# UV_Sheet1.net
KiCad netlist of a schematic drawn in Altium Designer
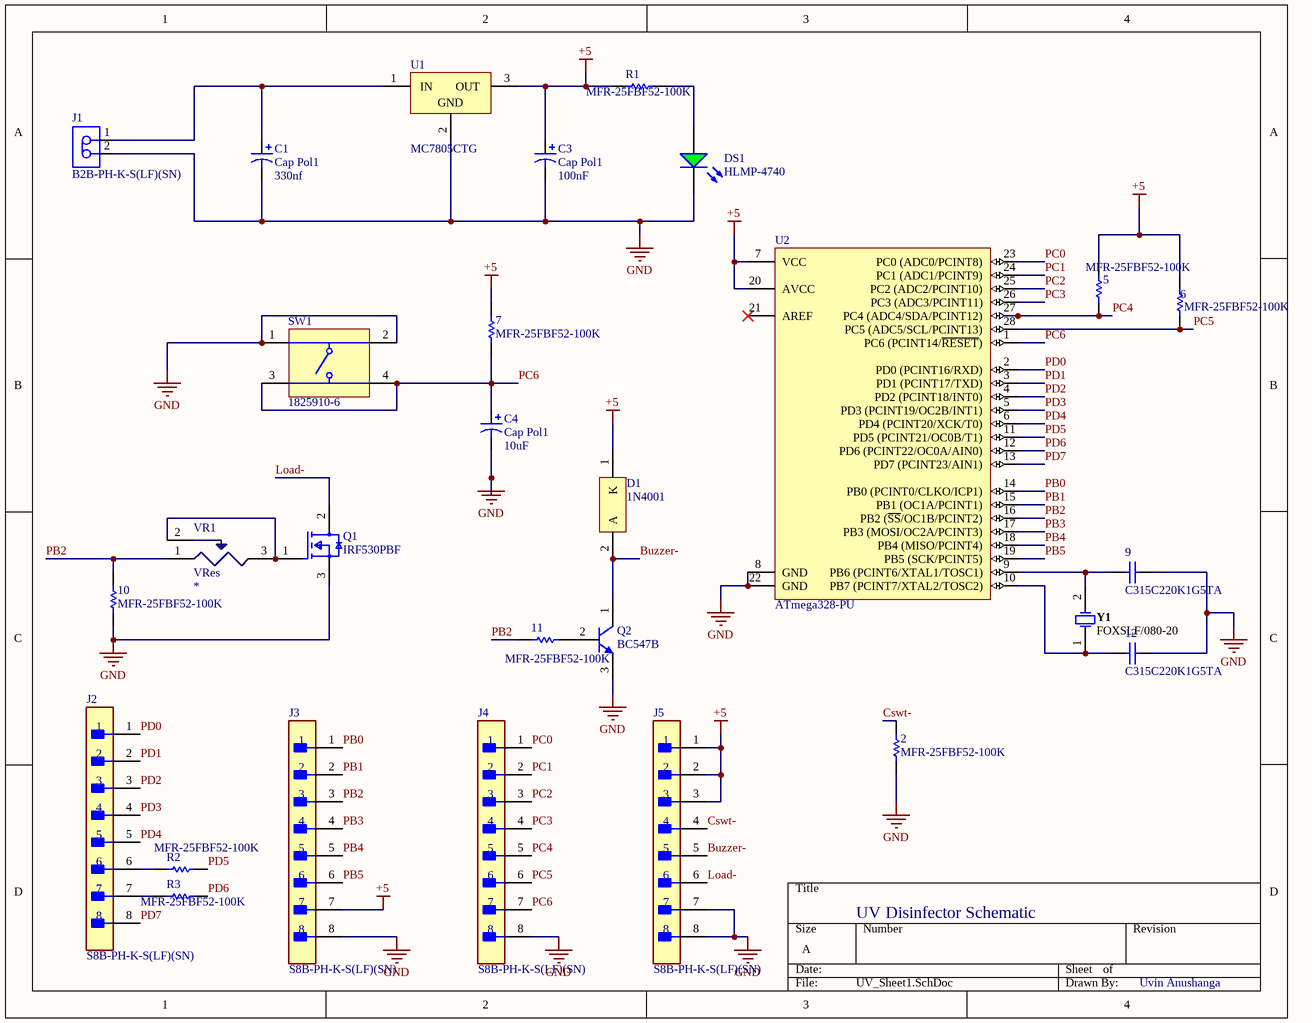
[diagram p0: UV_Sheet1.SchDoc]

(export (version "E")
  (design (tool "Eeschema 10.0.6"))
  (components
    (comp (ref "2")
      (value "MFR-25FBF52-100K")
      (footprint "RESA60-630X240")
      (description "Axial Resistor, 100 KOhm, +/- 1%, 0.25 W, -55 to 155 degC, 2-Pin THD, RoHS, Bulk")
      (fields (field (name "TOLERANCE") "1%"))
      (libsource (lib "Altium Content Vault") (part "RES-2"))
    )
    (comp (ref "5")
      (value "MFR-25FBF52-100K")
      (footprint "RESA60-630X240")
      (description "Axial Resistor, 100 KOhm, +/- 1%, 0.25 W, -55 to 155 degC, 2-Pin THD, RoHS, Bulk")
      (fields (field (name "TOLERANCE") "1%"))
      (libsource (lib "Altium Content Vault") (part "RES-2"))
    )
    (comp (ref "6")
      (value "MFR-25FBF52-100K")
      (footprint "RESA60-630X240")
      (description "Axial Resistor, 100 KOhm, +/- 1%, 0.25 W, -55 to 155 degC, 2-Pin THD, RoHS, Bulk")
      (fields (field (name "TOLERANCE") "1%"))
      (libsource (lib "Altium Content Vault") (part "RES-2"))
    )
    (comp (ref "7")
      (value "MFR-25FBF52-100K")
      (footprint "RESA60-630X240")
      (description "Axial Resistor, 100 KOhm, +/- 1%, 0.25 W, -55 to 155 degC, 2-Pin THD, RoHS, Bulk")
      (fields (field (name "TOLERANCE") "1%"))
      (libsource (lib "Altium Content Vault") (part "RES-2"))
    )
    (comp (ref "9")
      (value "C315C220K1G5TA")
      (footprint "KEMT-C315-THT-2")
      (description "Capacitor, Ceramic, 22 pF, +/-10 %, 100 V, -55 to 125 degC, 2-Pin THD, RoHS, Bulk")
      (libsource (lib "Altium Content Vault") (part "CAP-NP-2"))
    )
    (comp (ref "10")
      (value "MFR-25FBF52-100K")
      (footprint "RESA60-630X240")
      (description "Axial Resistor, 100 KOhm, +/- 1%, 0.25 W, -55 to 155 degC, 2-Pin THD, RoHS, Bulk")
      (fields (field (name "TOLERANCE") "1%"))
      (libsource (lib "Altium Content Vault") (part "RES-2"))
    )
    (comp (ref "11")
      (value "MFR-25FBF52-100K")
      (footprint "RESA60-630X240")
      (description "Axial Resistor, 100 KOhm, +/- 1%, 0.25 W, -55 to 155 degC, 2-Pin THD, RoHS, Bulk")
      (fields (field (name "TOLERANCE") "1%"))
      (libsource (lib "Altium Content Vault") (part "RES-2"))
    )
    (comp (ref "12")
      (value "C315C220K1G5TA")
      (footprint "KEMT-C315-THT-2")
      (description "Capacitor, Ceramic, 22 pF, +/-10 %, 100 V, -55 to 125 degC, 2-Pin THD, RoHS, Bulk")
      (libsource (lib "Altium Content Vault") (part "CAP-NP-2"))
    )
    (comp (ref "C1")
      (value "Cap Pol1")
      (footprint "RB7.6-15")
      (description "Polarized Capacitor (Radial)")
      (fields (field (name "ALTIUM_VALUE") "330nf") (field (name "PUBLISHER") "Altium Limited"))
      (libsource (lib "Miscellaneous Devices") (part "Cap Pol1"))
    )
    (comp (ref "C3")
      (value "Cap Pol1")
      (footprint "RB7.6-15")
      (description "Polarized Capacitor (Radial)")
      (fields (field (name "ALTIUM_VALUE") "100nF") (field (name "PUBLISHER") "Altium Limited"))
      (libsource (lib "Miscellaneous Devices") (part "Cap Pol1"))
    )
    (comp (ref "C4")
      (value "Cap Pol1")
      (footprint "RB7.6-15")
      (description "Polarized Capacitor (Radial)")
      (fields (field (name "ALTIUM_VALUE") "10uF") (field (name "PUBLISHER") "Altium Limited"))
      (libsource (lib "Miscellaneous Devices") (part "Cap Pol1"))
    )
    (comp (ref "D1")
      (value "1N4001")
      (footprint "ONSC-AXIAL_LEAD-2-59-10_P")
      (description "Standard Recovery Rectifier, 2-Pin Axial_Lead, Pb-Free, Bulk Bag")
      (fields (field (name "MANUFACTURER") "On Semiconductor"))
      (libsource (lib "Altium Content Vault") (part "ONSC-D-K1A2-2_A"))
    )
    (comp (ref "DS1")
      (value "HLMP-4740")
      (footprint "AVAG-HLMP-4740")
      (description "T-1 3/4 (5 mm) Low Current LED Lamp, Green, 1.9 V, -20 to 100 degC, 2-Pin THD, RoHS, Bulk")
      (fields (field (name "MANUFACTURER") "AvagoTechnologies"))
      (libsource (lib "Altium Content Vault") (part "LED-GREEN-AK-2"))
    )
    (comp (ref "J1")
      (value "B2B-PH-K-S(LF)(SN)")
      (footprint "JST-B2B-PH-K-S_V")
      (fields (field (name "MANUFACTURER") "JST"))
      (libsource (lib "Altium Content Vault") (part "CN-2P-F-QF2"))
    )
    (comp (ref "J2")
      (value "S8B-PH-K-S(LF)(SN)")
      (footprint "FP-S8B-PH-K-S_LF_SN-MFG")
      (description "CONN HEADER R/A 8POS 2MM")
      (libsource (lib "Altium Content Vault") (part "99ec2b232beb5d2356d4d77f6a047f0"))
    )
    (comp (ref "J3")
      (value "S8B-PH-K-S(LF)(SN)")
      (footprint "FP-S8B-PH-K-S_LF_SN-MFG")
      (description "CONN HEADER R/A 8POS 2MM")
      (libsource (lib "Altium Content Vault") (part "99ec2b232beb5d2356d4d77f6a047f0"))
    )
    (comp (ref "J4")
      (value "S8B-PH-K-S(LF)(SN)")
      (footprint "FP-S8B-PH-K-S_LF_SN-MFG")
      (description "CONN HEADER R/A 8POS 2MM")
      (libsource (lib "Altium Content Vault") (part "99ec2b232beb5d2356d4d77f6a047f0"))
    )
    (comp (ref "J5")
      (value "S8B-PH-K-S(LF)(SN)")
      (footprint "FP-S8B-PH-K-S_LF_SN-MFG")
      (description "CONN HEADER R/A 8POS 2MM")
      (libsource (lib "Altium Content Vault") (part "99ec2b232beb5d2356d4d77f6a047f0"))
    )
    (comp (ref "Q1")
      (value "IRF530PBF")
      (footprint "FP-X15-0364-MFG")
      (description "MOSFET N-CH 100V 14A TO-220AB")
      (fields
        (field (name "MANUFACTURER") "Vishay")
        (field (name "OCTOPART") "https://octopart.com/irf530pbf-vishay-46547999")
      )
      (libsource (lib "Altium Content Vault") (part "277670f45256a45703965f138927d09"))
    )
    (comp (ref "Q2")
      (value "BC547B")
      (footprint "ONSC-TO-92-3-29-11")
      (description "Amplifier Transistor, NPN Silicon, 3-Pin TO-92, Bulk Box")
      (fields (field (name "MANUFACTURER") "On Semiconductor"))
      (libsource (lib "Altium Content Vault") (part "ONSC-NPN-C1B2E3-3"))
    )
    (comp (ref "R1")
      (value "MFR-25FBF52-100K")
      (footprint "RESA60-630X240")
      (description "Axial Resistor, 100 KOhm, +/- 1%, 0.25 W, -55 to 155 degC, 2-Pin THD, RoHS, Bulk")
      (fields (field (name "TOLERANCE") "1%"))
      (libsource (lib "Altium Content Vault") (part "RES-2"))
    )
    (comp (ref "R2")
      (value "MFR-25FBF52-100K")
      (footprint "RESA60-630X240")
      (description "Axial Resistor, 100 KOhm, +/- 1%, 0.25 W, -55 to 155 degC, 2-Pin THD, RoHS, Bulk")
      (fields (field (name "TOLERANCE") "1%"))
      (libsource (lib "Altium Content Vault") (part "RES-2"))
    )
    (comp (ref "R3")
      (value "MFR-25FBF52-100K")
      (footprint "RESA60-630X240")
      (description "Axial Resistor, 100 KOhm, +/- 1%, 0.25 W, -55 to 155 degC, 2-Pin THD, RoHS, Bulk")
      (fields (field (name "TOLERANCE") "1%"))
      (libsource (lib "Altium Content Vault") (part "RES-2"))
    )
    (comp (ref "SW1")
      (value "1825910-6")
      (footprint "TECO-1825910-6_V")
      (description "Tact Switch, SPST-NO, 0.05 A, -35 to 85 degC, 4-Pin THD, RoHS, Bulk")
      (fields (field (name "MANUFACTURER") "TE Connectivity"))
      (libsource (lib "Altium Content Vault") (part "SW-SPST-4_A"))
    )
    (comp (ref "U1")
      (value "MC7805CTG")
      (footprint "ONSC-TO-220-3-221AB-01")
      (description "Positive Voltage Regulator, 1 A, 5 V, 0 to 125 degC, 3-Pin TO-220, RoHS, Tube")
      (fields (field (name "MANUFACTURER") "ON Semiconductor"))
      (libsource (lib "Altium Content Vault") (part "ONSC-MC7805CTG-TO-220-3"))
    )
    (comp (ref "U2")
      (value "ATmega328-PU")
      (footprint "28P3")
      (libsource (lib "Altium Content Vault") (part "MC-8B-ATM48-IL28"))
    )
    (comp (ref "VR1")
      (value "VRes")
      (footprint "VerRes")
      (fields (field (name "ALTIUM_VALUE") "*"))
      (libsource (lib "Funcgen") (part "VRes"))
    )
    (comp (ref "Y1")
      (value "FOXSLF/080-20")
      (footprint "FOX-FOXSLF080-20")
      (description "Resistance Weld Thru-Hole Crystal, 8 MHz, +/- 50 ppm, 10 pF, -20 to 70 degC, 2-Pin THD, RoHS, Bulk")
      (fields (field (name "MANUFACTURER") "FOX Electronics") (field (name "TOLERANCE") "50ppm"))
      (libsource (lib "University of Moratuwa") (part "XTAL-1-2-2"))
    )
  )
  (nets
    (net (code "1") (name "+5") (class "Default")
      (node (ref "5") (pin "2") (pinfunction "2_2") (pintype "passive"))
      (node (ref "6") (pin "2") (pinfunction "2_2") (pintype "passive"))
      (node (ref "7") (pin "2") (pinfunction "2_2") (pintype "passive"))
      (node (ref "C3") (pin "1") (pinfunction "1_1") (pintype "passive"))
      (node (ref "D1") (pin "1") (pinfunction "K_1") (pintype "passive"))
      (node (ref "J3") (pin "7") (pinfunction "7_7") (pintype "passive"))
      (node (ref "J5") (pin "1") (pinfunction "1_1") (pintype "passive"))
      (node (ref "J5") (pin "2") (pinfunction "2_2") (pintype "passive"))
      (node (ref "J5") (pin "3") (pinfunction "3_3") (pintype "passive"))
      (node (ref "R1") (pin "1") (pinfunction "1_1") (pintype "passive"))
      (node (ref "U1") (pin "3") (pinfunction "OUT_3") (pintype "power_in"))
      (node (ref "U2") (pin "20") (pinfunction "AVCC_20") (pintype "power_in"))
      (node (ref "U2") (pin "7") (pinfunction "VCC_7") (pintype "power_in"))
    )
    (net (code "2") (name "/Buzzer-") (class "Default")
      (node (ref "D1") (pin "2") (pinfunction "A_2") (pintype "passive"))
      (node (ref "J5") (pin "5") (pinfunction "5_5") (pintype "passive"))
      (node (ref "Q2") (pin "1") (pinfunction "C_1") (pintype "passive"))
    )
    (net (code "3") (name "/Cswt-") (class "Default")
      (node (ref "2") (pin "2") (pinfunction "2_2") (pintype "passive"))
      (node (ref "J5") (pin "4") (pinfunction "4_4") (pintype "passive"))
    )
    (net (code "4") (name "/Load-") (class "Default")
      (node (ref "J5") (pin "6") (pinfunction "6_6") (pintype "passive"))
      (node (ref "Q1") (pin "2") (pinfunction "D_2") (pintype "passive"))
    )
    (net (code "5") (name "/PB0") (class "Default")
      (node (ref "J3") (pin "1") (pinfunction "1_1") (pintype "passive"))
      (node (ref "U2") (pin "14") (pinfunction "PB0_(PCINT0/CLKO/ICP1)_14") (pintype "bidirectional"))
    )
    (net (code "6") (name "/PB1") (class "Default")
      (node (ref "J3") (pin "2") (pinfunction "2_2") (pintype "passive"))
      (node (ref "U2") (pin "15") (pinfunction "PB1_(OC1A/PCINT1)_15") (pintype "bidirectional"))
    )
    (net (code "7") (name "/PB2") (class "Default")
      (node (ref "10") (pin "2") (pinfunction "2_2") (pintype "passive"))
      (node (ref "11") (pin "1") (pinfunction "1_1") (pintype "passive"))
      (node (ref "J3") (pin "3") (pinfunction "3_3") (pintype "passive"))
      (node (ref "U2") (pin "16") (pinfunction "PB2_(~{SS}/OC1B/PCINT2)_16") (pintype "bidirectional"))
      (node (ref "VR1") (pin "1") (pinfunction "1_1") (pintype "passive"))
    )
    (net (code "8") (name "/PB3") (class "Default")
      (node (ref "J3") (pin "4") (pinfunction "4_4") (pintype "passive"))
      (node (ref "U2") (pin "17") (pinfunction "PB3_(MOSI/OC2A/PCINT3)_17") (pintype "bidirectional"))
    )
    (net (code "9") (name "/PB4") (class "Default")
      (node (ref "J3") (pin "5") (pinfunction "5_5") (pintype "passive"))
      (node (ref "U2") (pin "18") (pinfunction "PB4_(MISO/PCINT4)_18") (pintype "bidirectional"))
    )
    (net (code "10") (name "/PB5") (class "Default")
      (node (ref "J3") (pin "6") (pinfunction "6_6") (pintype "passive"))
      (node (ref "U2") (pin "19") (pinfunction "PB5_(SCK/PCINT5)_19") (pintype "bidirectional"))
    )
    (net (code "11") (name "/PC0") (class "Default")
      (node (ref "J4") (pin "1") (pinfunction "1_1") (pintype "passive"))
      (node (ref "U2") (pin "23") (pinfunction "PC0_(ADC0/PCINT8)_23") (pintype "bidirectional"))
    )
    (net (code "12") (name "/PC1") (class "Default")
      (node (ref "J4") (pin "2") (pinfunction "2_2") (pintype "passive"))
      (node (ref "U2") (pin "24") (pinfunction "PC1_(ADC1/PCINT9)_24") (pintype "bidirectional"))
    )
    (net (code "13") (name "/PC2") (class "Default")
      (node (ref "J4") (pin "3") (pinfunction "3_3") (pintype "passive"))
      (node (ref "U2") (pin "25") (pinfunction "PC2_(ADC2/PCINT10)_25") (pintype "bidirectional"))
    )
    (net (code "14") (name "/PC3") (class "Default")
      (node (ref "J4") (pin "4") (pinfunction "4_4") (pintype "passive"))
      (node (ref "U2") (pin "26") (pinfunction "PC3_(ADC3/PCINT11)_26") (pintype "bidirectional"))
    )
    (net (code "15") (name "/PC4") (class "Default")
      (node (ref "5") (pin "1") (pinfunction "1_1") (pintype "passive"))
      (node (ref "J4") (pin "5") (pinfunction "5_5") (pintype "passive"))
      (node (ref "U2") (pin "27") (pinfunction "PC4_(ADC4/SDA/PCINT12)_27") (pintype "bidirectional"))
    )
    (net (code "16") (name "/PC5") (class "Default")
      (node (ref "6") (pin "1") (pinfunction "1_1") (pintype "passive"))
      (node (ref "J4") (pin "6") (pinfunction "6_6") (pintype "passive"))
      (node (ref "U2") (pin "28") (pinfunction "PC5_(ADC5/SCL/PCINT13)_28") (pintype "bidirectional"))
    )
    (net (code "17") (name "/PC6") (class "Default")
      (node (ref "7") (pin "1") (pinfunction "1_1") (pintype "passive"))
      (node (ref "C4") (pin "1") (pinfunction "1_1") (pintype "passive"))
      (node (ref "J4") (pin "7") (pinfunction "7_7") (pintype "passive"))
      (node (ref "SW1") (pin "3") (pinfunction "3_3") (pintype "passive"))
      (node (ref "SW1") (pin "4") (pinfunction "4_4") (pintype "passive"))
      (node (ref "U2") (pin "1") (pinfunction "PC6_(PCINT14/~{RESET})_1") (pintype "bidirectional"))
    )
    (net (code "18") (name "/PD0") (class "Default")
      (node (ref "J2") (pin "1") (pinfunction "1_1") (pintype "passive"))
      (node (ref "U2") (pin "2") (pinfunction "PD0_(PCINT16/RXD)_2") (pintype "bidirectional"))
    )
    (net (code "19") (name "/PD1") (class "Default")
      (node (ref "J2") (pin "2") (pinfunction "2_2") (pintype "passive"))
      (node (ref "U2") (pin "3") (pinfunction "PD1_(PCINT17/TXD)_3") (pintype "bidirectional"))
    )
    (net (code "20") (name "/PD2") (class "Default")
      (node (ref "J2") (pin "3") (pinfunction "3_3") (pintype "passive"))
      (node (ref "U2") (pin "4") (pinfunction "PD2_(PCINT18/INT0)_4") (pintype "bidirectional"))
    )
    (net (code "21") (name "/PD3") (class "Default")
      (node (ref "J2") (pin "4") (pinfunction "4_4") (pintype "passive"))
      (node (ref "U2") (pin "5") (pinfunction "PD3_(PCINT19/OC2B/INT1)_5") (pintype "bidirectional"))
    )
    (net (code "22") (name "/PD4") (class "Default")
      (node (ref "J2") (pin "5") (pinfunction "5_5") (pintype "passive"))
      (node (ref "U2") (pin "6") (pinfunction "PD4_(PCINT20/XCK/T0)_6") (pintype "bidirectional"))
    )
    (net (code "23") (name "/PD5") (class "Default")
      (node (ref "R2") (pin "2") (pinfunction "2_2") (pintype "passive"))
      (node (ref "U2") (pin "11") (pinfunction "PD5_(PCINT21/OC0B/T1)_11") (pintype "bidirectional"))
    )
    (net (code "24") (name "/PD6") (class "Default")
      (node (ref "R3") (pin "2") (pinfunction "2_2") (pintype "passive"))
      (node (ref "U2") (pin "12") (pinfunction "PD6_(PCINT22/OC0A/AIN0)_12") (pintype "bidirectional"))
    )
    (net (code "25") (name "/PD7") (class "Default")
      (node (ref "J2") (pin "8") (pinfunction "8_8") (pintype "passive"))
      (node (ref "U2") (pin "13") (pinfunction "PD7_(PCINT23/AIN1)_13") (pintype "bidirectional"))
    )
    (net (code "26") (name "GND") (class "Default")
      (node (ref "10") (pin "1") (pinfunction "1_1") (pintype "passive"))
      (node (ref "12") (pin "2") (pinfunction "2_2") (pintype "passive"))
      (node (ref "2") (pin "1") (pinfunction "1_1") (pintype "passive"))
      (node (ref "9") (pin "2") (pinfunction "2_2") (pintype "passive"))
      (node (ref "C1") (pin "2") (pinfunction "2_2") (pintype "passive"))
      (node (ref "C3") (pin "2") (pinfunction "2_2") (pintype "passive"))
      (node (ref "C4") (pin "2") (pinfunction "2_2") (pintype "passive"))
      (node (ref "DS1") (pin "2") (pinfunction "K_2") (pintype "passive"))
      (node (ref "J1") (pin "2") (pinfunction "2_2") (pintype "passive"))
      (node (ref "J3") (pin "8") (pinfunction "8_8") (pintype "passive"))
      (node (ref "J4") (pin "8") (pinfunction "8_8") (pintype "passive"))
      (node (ref "J5") (pin "7") (pinfunction "7_7") (pintype "passive"))
      (node (ref "J5") (pin "8") (pinfunction "8_8") (pintype "passive"))
      (node (ref "Q1") (pin "3") (pinfunction "S_3") (pintype "passive"))
      (node (ref "Q2") (pin "3") (pinfunction "E_3") (pintype "passive"))
      (node (ref "SW1") (pin "1") (pinfunction "1_1") (pintype "passive"))
      (node (ref "SW1") (pin "2") (pinfunction "2_2") (pintype "passive"))
      (node (ref "U1") (pin "2") (pinfunction "GND_2") (pintype "power_in"))
      (node (ref "U2") (pin "22") (pinfunction "GND_22") (pintype "power_in"))
      (node (ref "U2") (pin "8") (pinfunction "GND_8") (pintype "power_in"))
    )
    (net (code "27") (name "Net-(DS1-A)") (class "Default")
      (node (ref "DS1") (pin "1") (pinfunction "A_1") (pintype "passive"))
      (node (ref "R1") (pin "2") (pinfunction "2_2") (pintype "passive"))
    )
    (net (code "28") (name "Net-(J2-Pad6)") (class "Default")
      (node (ref "J2") (pin "6") (pinfunction "6_6") (pintype "passive"))
      (node (ref "R2") (pin "1") (pinfunction "1_1") (pintype "passive"))
    )
    (net (code "29") (name "Net-(J2-Pad7)") (class "Default")
      (node (ref "J2") (pin "7") (pinfunction "7_7") (pintype "passive"))
      (node (ref "R3") (pin "1") (pinfunction "1_1") (pintype "passive"))
    )
    (net (code "30") (name "Net-(Q1-G)") (class "Default")
      (node (ref "Q1") (pin "1") (pinfunction "G_1") (pintype "passive"))
      (node (ref "VR1") (pin "2") (pinfunction "2_2") (pintype "passive"))
      (node (ref "VR1") (pin "3") (pinfunction "3_3") (pintype "passive"))
    )
    (net (code "31") (name "Net-(Q2-B)") (class "Default")
      (node (ref "11") (pin "2") (pinfunction "2_2") (pintype "passive"))
      (node (ref "Q2") (pin "2") (pinfunction "B_2") (pintype "passive"))
    )
    (net (code "32") (name "Net-(U1-IN)") (class "Default")
      (node (ref "C1") (pin "1") (pinfunction "1_1") (pintype "passive"))
      (node (ref "J1") (pin "1") (pinfunction "1_1") (pintype "passive"))
      (node (ref "U1") (pin "1") (pinfunction "IN_1") (pintype "power_in"))
    )
    (net (code "33") (name "Net-(U2-PB6_(PCINT6{slash}XTAL1{slash}TOSC1))") (class "Default")
      (node (ref "9") (pin "1") (pinfunction "1_1") (pintype "passive"))
      (node (ref "U2") (pin "9") (pinfunction "PB6_(PCINT6/XTAL1/TOSC1)_9") (pintype "bidirectional"))
      (node (ref "Y1") (pin "2") (pinfunction "2_2") (pintype "passive"))
    )
    (net (code "34") (name "Net-(U2-PB7_(PCINT7{slash}XTAL2{slash}TOSC2))") (class "Default")
      (node (ref "12") (pin "1") (pinfunction "1_1") (pintype "passive"))
      (node (ref "U2") (pin "10") (pinfunction "PB7_(PCINT7/XTAL2/TOSC2)_10") (pintype "bidirectional"))
      (node (ref "Y1") (pin "1") (pinfunction "1_1") (pintype "passive"))
    )
    (net (code "35") (name "unconnected-(U2-AREF-Pad21)") (class "Default")
      (node (ref "U2") (pin "21") (pinfunction "AREF_21") (pintype "power_in+no_connect"))
    )
  )
)
